# C.net
KiCad netlist of a schematic drawn in EasyEDA Pro
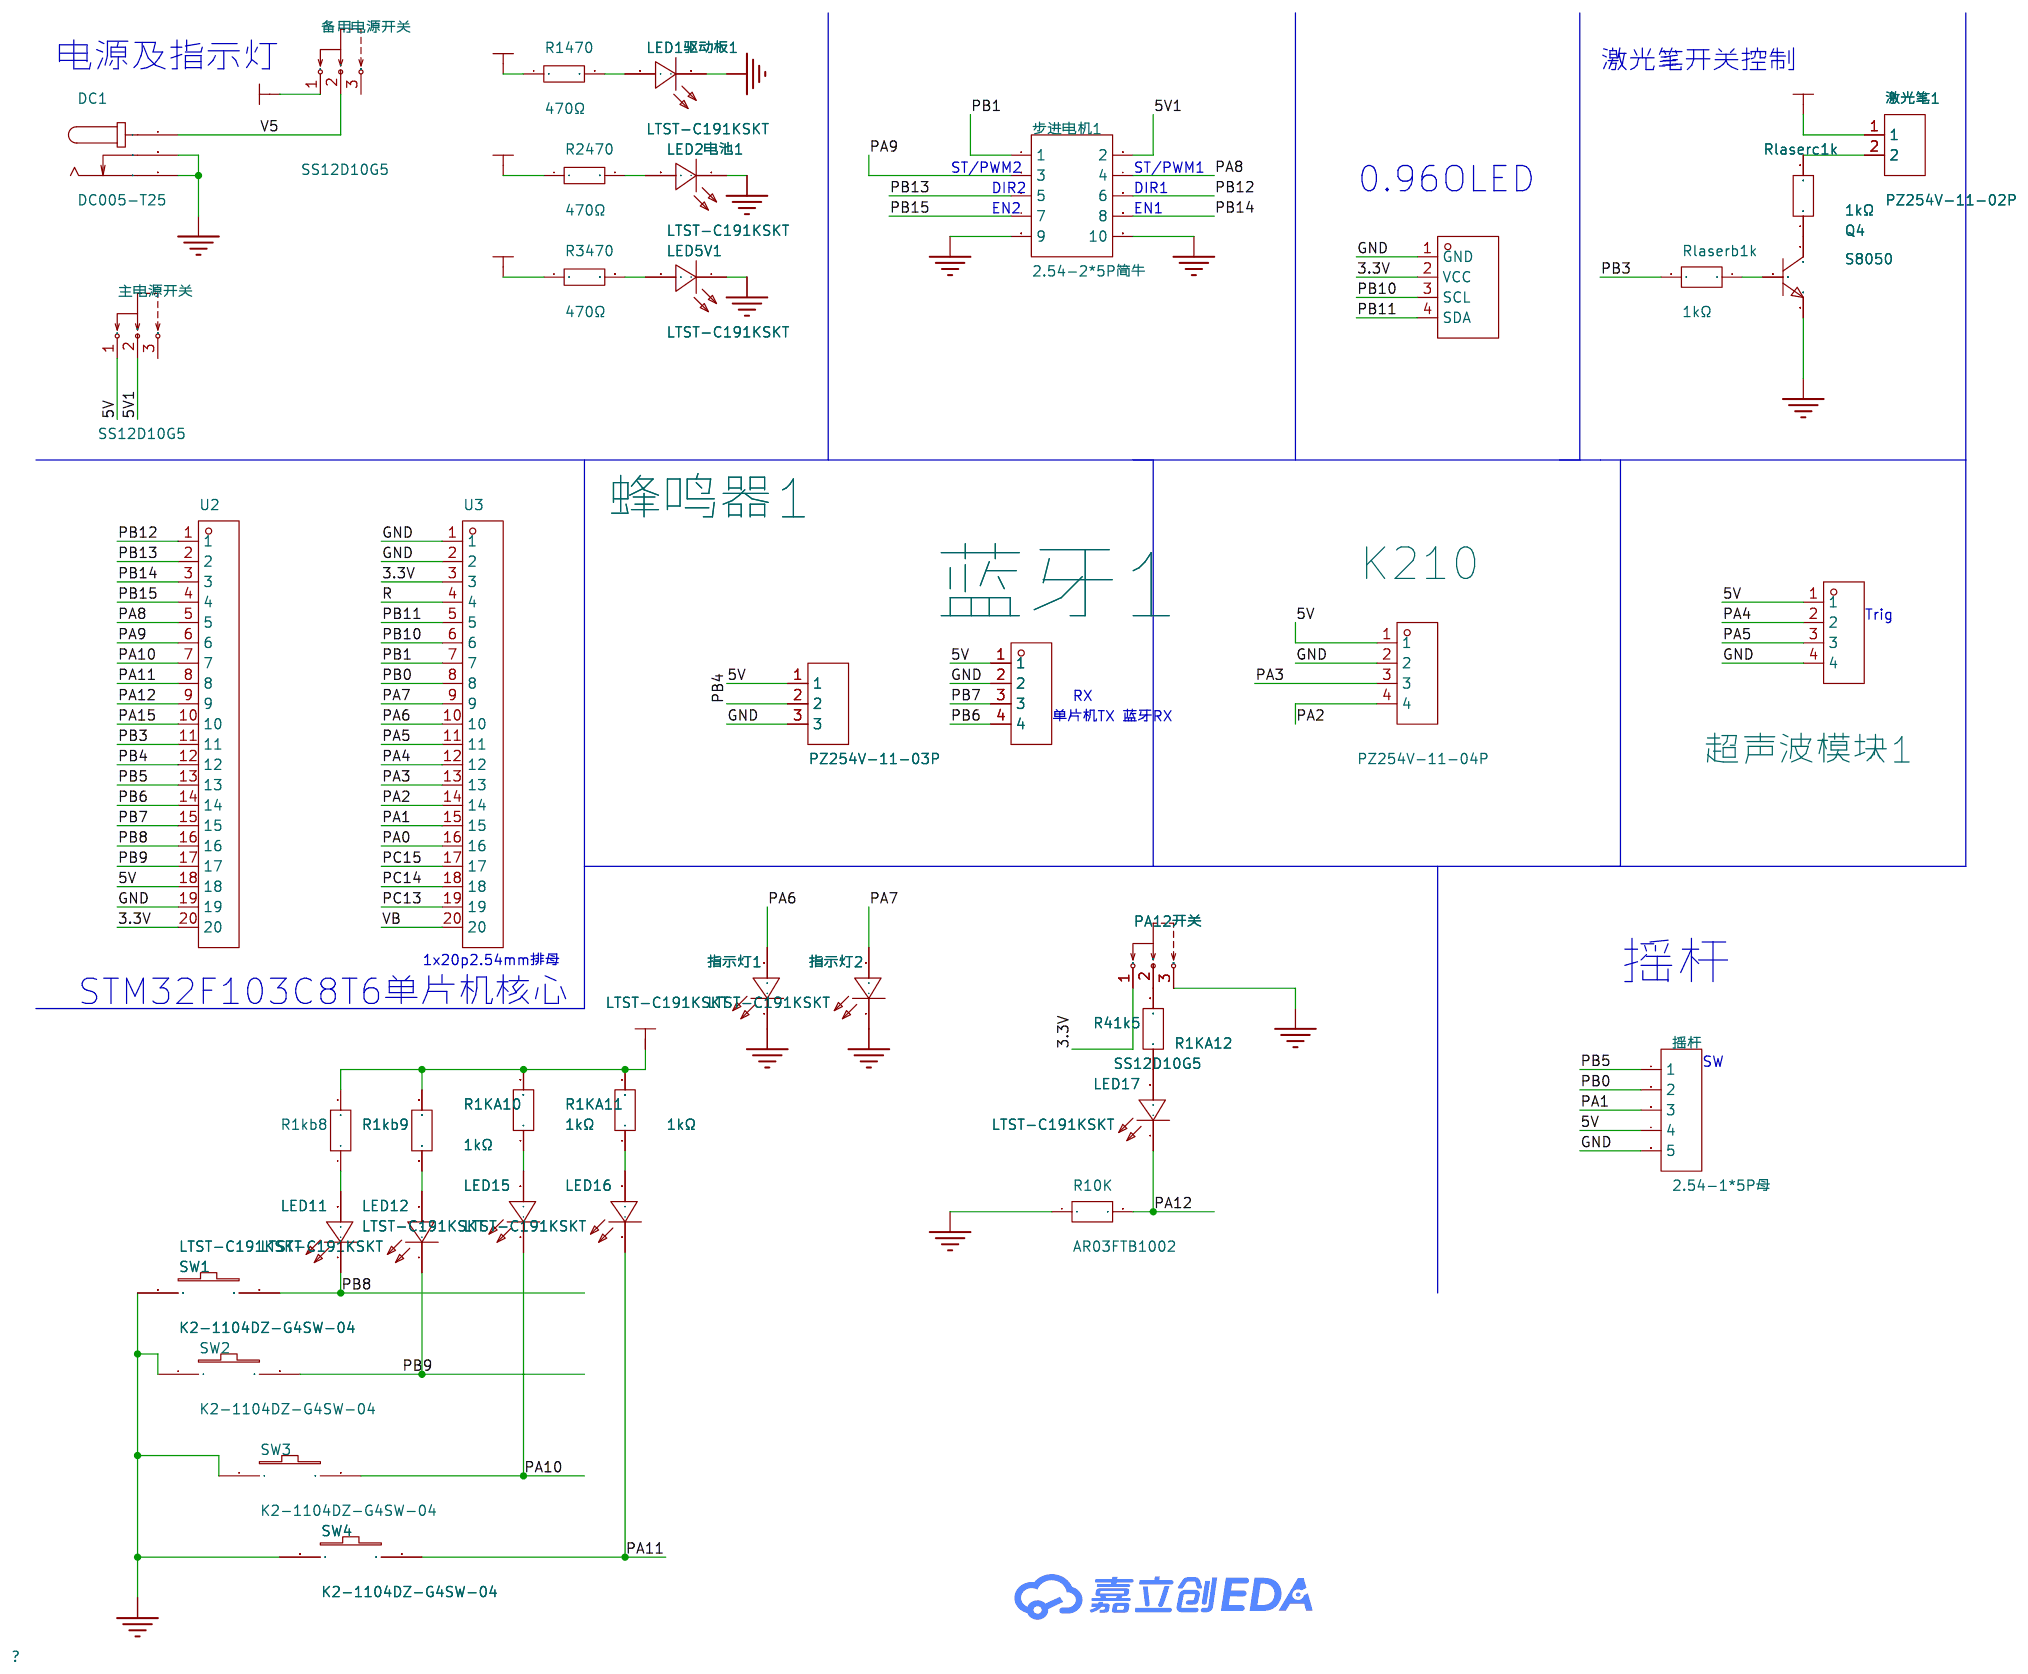
[diagram p0: schematic sheet]

(export (version "E")
  (design (tool "Eeschema 10.0.6"))
  (components
    (comp (ref "DC1")
      (value "DC005-T25")
      (footprint "easyedapro:DC-IN-TH_DC-005-20A-1")
      (description "触点内径:2.5mm;触点外径:6.3mm;额定电流:-;额定电压:-;")
      (fields (field (name "Manufacturer") "SOFNG(硕方)"))
      (libsource (lib "easyedapro") (part "DC005-2.5MM"))
    )
    (comp (ref "K210")
      (value "PZ254V-11-04P")
      (footprint "easyedapro:HDR-TH_4P-P2.54-V-M")
      (fields (field (name "Manufacturer") "XFCN(兴飞)"))
      (libsource (lib "easyedapro") (part "PZ254V-11-04P_C2691448"))
    )
    (comp (ref "LED1驱动板1")
      (value "LTST-C191KSKT")
      (footprint "easyedapro:LED0603-RD-YELLOW")
      (fields (field (name "Manufacturer") "LITEON(光宝)"))
      (libsource (lib "easyedapro") (part "LTST-C191KSKT"))
    )
    (comp (ref "LED2电池1")
      (value "LTST-C191KSKT")
      (footprint "easyedapro:LED0603-RD-YELLOW")
      (fields (field (name "Manufacturer") "LITEON(光宝)"))
      (libsource (lib "easyedapro") (part "LTST-C191KSKT"))
    )
    (comp (ref "LED5V1")
      (value "LTST-C191KSKT")
      (footprint "easyedapro:LED0603-RD-YELLOW")
      (fields (field (name "Manufacturer") "LITEON(光宝)"))
      (libsource (lib "easyedapro") (part "LTST-C191KSKT"))
    )
    (comp (ref "LED11")
      (value "LTST-C191KSKT")
      (footprint "easyedapro:LED0603-RD-YELLOW")
      (fields (field (name "Manufacturer") "LITEON(光宝)"))
      (libsource (lib "easyedapro") (part "LTST-C191KSKT"))
    )
    (comp (ref "LED12")
      (value "LTST-C191KSKT")
      (footprint "easyedapro:LED0603-RD-YELLOW")
      (fields (field (name "Manufacturer") "LITEON(光宝)"))
      (libsource (lib "easyedapro") (part "LTST-C191KSKT"))
    )
    (comp (ref "LED15")
      (value "LTST-C191KSKT")
      (footprint "easyedapro:LED0603-RD-YELLOW")
      (fields (field (name "Manufacturer") "LITEON(光宝)"))
      (libsource (lib "easyedapro") (part "LTST-C191KSKT"))
    )
    (comp (ref "LED16")
      (value "LTST-C191KSKT")
      (footprint "easyedapro:LED0603-RD-YELLOW")
      (fields (field (name "Manufacturer") "LITEON(光宝)"))
      (libsource (lib "easyedapro") (part "LTST-C191KSKT"))
    )
    (comp (ref "LED17")
      (value "LTST-C191KSKT")
      (footprint "easyedapro:LED0603-RD-YELLOW")
      (fields (field (name "Manufacturer") "LITEON(光宝)"))
      (libsource (lib "easyedapro") (part "LTST-C191KSKT"))
    )
    (comp (ref "OLED1")
      (value "HS96L03W2C03")
      (footprint "easyedapro:OLED-TH_L27.8-W27.2-P2.54_C9900033791")
      (description "主控芯片:SSD1315;接口类型:I2C;尺寸(inch):0.96;像素分辨率:128x64;")
      (fields (field (name "Manufacturer") "HS(汉昇)"))
      (libsource (lib "easyedapro") (part "HS96L03W2C03"))
    )
    (comp (ref "PA12开关")
      (value "SS12D10G5")
      (footprint "easyedapro:SW-TH_SHOU-HAN_SS12D10G4")
      (description "电路结构:单刀双掷;安装方式:直插;额定电流(DC):2A;额定电压(DC):125V;机械寿命:3千次;")
      (fields (field (name "Manufacturer") "SHOU HAN(首韩)"))
      (libsource (lib "easyedapro") (part "SS12D10G5"))
    )
    (comp (ref "Q4")
      (value "S8050")
      (footprint "easyedapro:SOT-23-3_L2.9-W1.6-P1.90-LS2.8-BR")
      (description "晶体管类型:NPN;集电极电流(Ic):500mA;集射极击穿电压(Vceo):25V;功率(Pd):300mW;")
      (fields (field (name "Manufacturer") "Hottech(合科泰)"))
      (libsource (lib "easyedapro") (part "S8050_C181158"))
    )
    (comp (ref "R1KA10")
      (value "1kΩ")
      (footprint "easyedapro:R0603")
      (description "电阻类型:厚膜电阻;阻值:1kΩ;精度:±1%;功率:100mW;最大工作电压:75V;")
      (fields (field (name "Manufacturer Part") "FCR0603F1K") (field (name "Manufacturer") "VO(翔胜)"))
      (libsource (lib "easyedapro") (part "FCR0603F1K"))
    )
    (comp (ref "R1KA11")
      (value "1kΩ")
      (footprint "easyedapro:R0603")
      (description "电阻类型:厚膜电阻;阻值:1kΩ;精度:±1%;功率:100mW;最大工作电压:75V;")
      (fields (field (name "Manufacturer Part") "FCR0603F1K") (field (name "Manufacturer") "VO(翔胜)"))
      (libsource (lib "easyedapro") (part "FCR0603F1K"))
    )
    (comp (ref "R1kb8")
      (value "1kΩ")
      (footprint "easyedapro:R0603")
      (description "电阻类型:厚膜电阻;阻值:1kΩ;精度:±1%;功率:100mW;最大工作电压:75V;")
      (fields (field (name "Manufacturer Part") "FCR0603F1K") (field (name "Manufacturer") "VO(翔胜)"))
      (libsource (lib "easyedapro") (part "FCR0603F1K"))
    )
    (comp (ref "R1kb9")
      (value "1kΩ")
      (footprint "easyedapro:R0603")
      (description "电阻类型:厚膜电阻;阻值:1kΩ;精度:±1%;功率:100mW;最大工作电压:75V;")
      (fields (field (name "Manufacturer Part") "FCR0603F1K") (field (name "Manufacturer") "VO(翔胜)"))
      (libsource (lib "easyedapro") (part "FCR0603F1K"))
    )
    (comp (ref "R10K")
      (value "AR03FTB1002")
      (footprint "easyedapro:R0603")
      (fields (field (name "Manufacturer") "Viking(光颉)"))
      (libsource (lib "easyedapro") (part "AR03FTB1002"))
    )
    (comp (ref "R41k5")
      (value "1kΩ")
      (footprint "easyedapro:R0603")
      (description "电阻类型:厚膜电阻;阻值:1kΩ;精度:±1%;功率:100mW;最大工作电压:75V;")
      (fields (field (name "Manufacturer Part") "FCR0603F1K") (field (name "Manufacturer") "VO(翔胜)"))
      (libsource (lib "easyedapro") (part "FCR0603F1K"))
    )
    (comp (ref "R1470")
      (value "470Ω")
      (footprint "easyedapro:R0603")
      (description "电阻类型:厚膜电阻;阻值:470Ω;精度:±1%;功率:100mW;最大工作电压:75V;温度系数:±100ppm/°C;")
      (fields
        (field (name "Manufacturer Part") "0603WAF4700T5E")
        (field (name "Manufacturer") "UNI-ROYAL(厚声)")
      )
      (libsource (lib "easyedapro") (part "0603WAF4700T5E"))
    )
    (comp (ref "R2470")
      (value "470Ω")
      (footprint "easyedapro:R0603")
      (description "电阻类型:厚膜电阻;阻值:470Ω;精度:±1%;功率:100mW;最大工作电压:75V;温度系数:±100ppm/°C;")
      (fields
        (field (name "Manufacturer Part") "0603WAF4700T5E")
        (field (name "Manufacturer") "UNI-ROYAL(厚声)")
      )
      (libsource (lib "easyedapro") (part "0603WAF4700T5E"))
    )
    (comp (ref "R3470")
      (value "470Ω")
      (footprint "easyedapro:R0603")
      (description "电阻类型:厚膜电阻;阻值:470Ω;精度:±1%;功率:100mW;最大工作电压:75V;温度系数:±100ppm/°C;")
      (fields
        (field (name "Manufacturer Part") "0603WAF4700T5E")
        (field (name "Manufacturer") "UNI-ROYAL(厚声)")
      )
      (libsource (lib "easyedapro") (part "0603WAF4700T5E"))
    )
    (comp (ref "Rlaserb1k")
      (value "1kΩ")
      (footprint "easyedapro:R0603")
      (description "电阻类型:厚膜电阻;阻值:1kΩ;精度:±1%;功率:100mW;最大工作电压:75V;")
      (fields (field (name "Manufacturer Part") "FCR0603F1K") (field (name "Manufacturer") "VO(翔胜)"))
      (libsource (lib "easyedapro") (part "FCR0603F1K"))
    )
    (comp (ref "Rlaserc1k")
      (value "1kΩ")
      (footprint "easyedapro:R0603")
      (description "电阻类型:厚膜电阻;阻值:1kΩ;精度:±1%;功率:100mW;最大工作电压:75V;")
      (fields (field (name "Manufacturer Part") "FCR0603F1K") (field (name "Manufacturer") "VO(翔胜)"))
      (libsource (lib "easyedapro") (part "FCR0603F1K"))
    )
    (comp (ref "SW1")
      (value "K2-1104DZ-G4SW-04")
      (footprint "easyedapro:KEY-TH_2P-L6.0-W6.0-P5.00")
      (description "作用力:250gf;安装方式:直插;开关长度:6mm;开关宽度:6mm;开关高度:7mm;触点电流:50mA;额定电压(DC):12V;绝缘电阻:100MΩ;机械寿命:10万次;")
      (fields (field (name "Manufacturer") "韩国韩荣"))
      (libsource (lib "easyedapro") (part "K2-1104DZ-G4SW-04"))
    )
    (comp (ref "SW2")
      (value "K2-1104DZ-G4SW-04")
      (footprint "easyedapro:KEY-TH_2P-L6.0-W6.0-P5.00")
      (description "作用力:250gf;安装方式:直插;开关长度:6mm;开关宽度:6mm;开关高度:7mm;触点电流:50mA;额定电压(DC):12V;绝缘电阻:100MΩ;机械寿命:10万次;")
      (fields (field (name "Manufacturer") "韩国韩荣"))
      (libsource (lib "easyedapro") (part "K2-1104DZ-G4SW-04"))
    )
    (comp (ref "SW3")
      (value "K2-1104DZ-G4SW-04")
      (footprint "easyedapro:KEY-TH_2P-L6.0-W6.0-P5.00")
      (description "作用力:250gf;安装方式:直插;开关长度:6mm;开关宽度:6mm;开关高度:7mm;触点电流:50mA;额定电压(DC):12V;绝缘电阻:100MΩ;机械寿命:10万次;")
      (fields (field (name "Manufacturer") "韩国韩荣"))
      (libsource (lib "easyedapro") (part "K2-1104DZ-G4SW-04"))
    )
    (comp (ref "SW4")
      (value "K2-1104DZ-G4SW-04")
      (footprint "easyedapro:KEY-TH_2P-L6.0-W6.0-P5.00")
      (description "作用力:250gf;安装方式:直插;开关长度:6mm;开关宽度:6mm;开关高度:7mm;触点电流:50mA;额定电压(DC):12V;绝缘电阻:100MΩ;机械寿命:10万次;")
      (fields (field (name "Manufacturer") "韩国韩荣"))
      (libsource (lib "easyedapro") (part "K2-1104DZ-G4SW-04"))
    )
    (comp (ref "U2")
      (value "KH-2FH-1X20P-H4.3")
      (footprint "easyedapro:HDR-TH_20P-P2.00-V-F-A")
      (fields (field (name "Manufacturer") "kinghelm(金航标)"))
      (libsource (lib "easyedapro") (part "KH-2FH-1X20P-H4.3"))
    )
    (comp (ref "U3")
      (value "KH-2FH-1X20P-H4.3")
      (footprint "easyedapro:HDR-TH_20P-P2.00-V-F-A")
      (fields (field (name "Manufacturer") "kinghelm(金航标)"))
      (libsource (lib "easyedapro") (part "KH-2FH-1X20P-H4.3"))
    )
    (comp (ref "主电源开关")
      (value "SS12D10G5")
      (footprint "easyedapro:SW-TH_SHOU-HAN_SS12D10G4")
      (description "电路结构:单刀双掷;安装方式:直插;额定电流(DC):2A;额定电压(DC):125V;机械寿命:3千次;")
      (fields (field (name "Manufacturer") "SHOU HAN(首韩)"))
      (libsource (lib "easyedapro") (part "SS12D10G5"))
    )
    (comp (ref "备用电源开关")
      (value "SS12D10G5")
      (footprint "easyedapro:SW-TH_SHOU-HAN_SS12D10G4")
      (description "电路结构:单刀双掷;安装方式:直插;额定电流(DC):2A;额定电压(DC):125V;机械寿命:3千次;")
      (fields (field (name "Manufacturer") "SHOU HAN(首韩)"))
      (libsource (lib "easyedapro") (part "SS12D10G5"))
    )
    (comp (ref "指示灯1")
      (value "LTST-C191KSKT")
      (footprint "easyedapro:LED0603-RD-YELLOW")
      (fields (field (name "Manufacturer") "LITEON(光宝)"))
      (libsource (lib "easyedapro") (part "LTST-C191KSKT"))
    )
    (comp (ref "指示灯2")
      (value "LTST-C191KSKT")
      (footprint "easyedapro:LED0603-RD-YELLOW")
      (fields (field (name "Manufacturer") "LITEON(光宝)"))
      (libsource (lib "easyedapro") (part "LTST-C191KSKT"))
    )
    (comp (ref "摇杆")
      (value "2.54-1*5P母")
      (footprint "easyedapro:HDR-TH_5P-P2.54-V-F")
      (description "插孔结构:1x5P;间距:2.54mm;行距:-;安装类型:直插;排数:单排;总孔位数:5P;塑高:-;触头材质:-;触头镀层:-;")
      (fields (field (name "Manufacturer") "BOOMELE(博穆精密)"))
      (libsource (lib "easyedapro") (part "Header-Female-2.54_1x5"))
    )
    (comp (ref "步进电机1")
      (value "2.54-2*5P简牛")
      (footprint "easyedapro:IDC-TH_10P-P2.54_C5665")
      (description "连接器类型:简牛座;间距:2.54mm;结构:2x5P;封装形式:直插;行距:2.54mm;排数:2;每排PIN数:5;触头材质:-;触头镀层:-;")
      (fields (field (name "Manufacturer") "BOOMELE(博穆精密)"))
      (libsource (lib "easyedapro") (part "HDR-IDC-2.54-2X5P"))
    )
    (comp (ref "激光笔1")
      (value "PZ254V-11-02P")
      (footprint "easyedapro:HDR-TH_2P-P2.54-V-M")
      (fields (field (name "Manufacturer") "XFCN(兴飞)"))
      (libsource (lib "easyedapro") (part "PZ254V-11-02P"))
    )
    (comp (ref "蓝牙1")
      (value "2.54-1*4P母")
      (footprint "easyedapro:HDR-TH_4P-P2.54-V-F")
      (fields (field (name "Manufacturer") "BOOMELE(博穆精密)"))
      (libsource (lib "easyedapro") (part "2.54-1*4P母"))
    )
    (comp (ref "蜂鸣器1")
      (value "PZ254V-11-03P")
      (footprint "easyedapro:HDR-TH_3P-P2.54-V-M")
      (fields (field (name "Manufacturer") "XFCN(兴飞)"))
      (libsource (lib "easyedapro") (part "PZ254V-11-03P_C2937625"))
    )
    (comp (ref "超声波模块1")
      (value "KH-2.54FH-1X4P-H8.5")
      (footprint "easyedapro:HDR-TH_4P-P2.54-V-F")
      (fields (field (name "Manufacturer") "kinghelm(金航标)"))
      (libsource (lib "easyedapro") (part "KH-2.54FH-1X4P-H8.5"))
    )
  )
  (nets
    (net (code "1") (name "/PA0") (class "Default")
      (node (ref "U3") (pin "16") (pinfunction "16_16") (pintype "unspecified"))
    )
    (net (code "2") (name "/PA1") (class "Default")
      (node (ref "U3") (pin "15") (pinfunction "15_15") (pintype "unspecified"))
      (node (ref "摇杆") (pin "3") (pinfunction "3_3") (pintype "input"))
    )
    (net (code "3") (name "/PA2") (class "Default")
      (node (ref "K210") (pin "4") (pinfunction "4_4") (pintype "unspecified"))
      (node (ref "U3") (pin "14") (pinfunction "14_14") (pintype "unspecified"))
    )
    (net (code "4") (name "/PA3") (class "Default")
      (node (ref "K210") (pin "3") (pinfunction "3_3") (pintype "unspecified"))
      (node (ref "U3") (pin "13") (pinfunction "13_13") (pintype "unspecified"))
    )
    (net (code "5") (name "/PA4") (class "Default")
      (node (ref "U3") (pin "12") (pinfunction "12_12") (pintype "unspecified"))
      (node (ref "超声波模块1") (pin "2") (pinfunction "2_2") (pintype "unspecified"))
    )
    (net (code "6") (name "/PA5") (class "Default")
      (node (ref "U3") (pin "11") (pinfunction "11_11") (pintype "unspecified"))
      (node (ref "超声波模块1") (pin "3") (pinfunction "3_3") (pintype "unspecified"))
    )
    (net (code "7") (name "/PA6") (class "Default")
      (node (ref "U3") (pin "10") (pinfunction "10_10") (pintype "unspecified"))
      (node (ref "指示灯1") (pin "2") (pinfunction "+_2") (pintype "unspecified"))
    )
    (net (code "8") (name "/PA7") (class "Default")
      (node (ref "U3") (pin "9") (pinfunction "9_9") (pintype "unspecified"))
      (node (ref "指示灯2") (pin "2") (pinfunction "+_2") (pintype "unspecified"))
    )
    (net (code "9") (name "/PA8") (class "Default")
      (node (ref "U2") (pin "5") (pinfunction "5_5") (pintype "unspecified"))
      (node (ref "步进电机1") (pin "4") (pinfunction "4_4") (pintype "unspecified"))
    )
    (net (code "10") (name "/PA9") (class "Default")
      (node (ref "U2") (pin "6") (pinfunction "6_6") (pintype "unspecified"))
      (node (ref "步进电机1") (pin "3") (pinfunction "3_3") (pintype "unspecified"))
    )
    (net (code "11") (name "/PA10") (class "Default")
      (node (ref "LED15") (pin "1") (pinfunction "-_1") (pintype "unspecified"))
      (node (ref "SW3") (pin "2") (pinfunction "2_2") (pintype "input"))
      (node (ref "U2") (pin "7") (pinfunction "7_7") (pintype "unspecified"))
    )
    (net (code "12") (name "/PA11") (class "Default")
      (node (ref "LED16") (pin "1") (pinfunction "-_1") (pintype "unspecified"))
      (node (ref "SW4") (pin "2") (pinfunction "2_2") (pintype "input"))
      (node (ref "U2") (pin "8") (pinfunction "8_8") (pintype "unspecified"))
    )
    (net (code "13") (name "/PA12") (class "Default")
      (node (ref "LED17") (pin "1") (pinfunction "-_1") (pintype "unspecified"))
      (node (ref "R10K") (pin "2") (pinfunction "2_2") (pintype "unspecified"))
      (node (ref "U2") (pin "9") (pinfunction "9_9") (pintype "unspecified"))
    )
    (net (code "14") (name "/PA15") (class "Default")
      (node (ref "U2") (pin "10") (pinfunction "10_10") (pintype "unspecified"))
    )
    (net (code "15") (name "/PB0") (class "Default")
      (node (ref "U3") (pin "8") (pinfunction "8_8") (pintype "unspecified"))
      (node (ref "摇杆") (pin "2") (pinfunction "2_2") (pintype "input"))
    )
    (net (code "16") (name "/PB1") (class "Default")
      (node (ref "U3") (pin "7") (pinfunction "7_7") (pintype "unspecified"))
      (node (ref "步进电机1") (pin "1") (pinfunction "1_1") (pintype "unspecified"))
    )
    (net (code "17") (name "/PB3") (class "Default")
      (node (ref "Rlaserb1k") (pin "2") (pinfunction "2_2") (pintype "unspecified"))
      (node (ref "U2") (pin "11") (pinfunction "11_11") (pintype "unspecified"))
    )
    (net (code "18") (name "/PB4") (class "Default")
      (node (ref "U2") (pin "12") (pinfunction "12_12") (pintype "unspecified"))
      (node (ref "蜂鸣器1") (pin "2") (pinfunction "2_2") (pintype "unspecified"))
    )
    (net (code "19") (name "/PB5") (class "Default")
      (node (ref "U2") (pin "13") (pinfunction "13_13") (pintype "unspecified"))
      (node (ref "摇杆") (pin "1") (pinfunction "1_1") (pintype "input"))
    )
    (net (code "20") (name "/PB6") (class "Default")
      (node (ref "U2") (pin "14") (pinfunction "14_14") (pintype "unspecified"))
      (node (ref "蓝牙1") (pin "4") (pinfunction "4_4") (pintype "unspecified"))
    )
    (net (code "21") (name "/PB7") (class "Default")
      (node (ref "U2") (pin "15") (pinfunction "15_15") (pintype "unspecified"))
      (node (ref "蓝牙1") (pin "3") (pinfunction "3_3") (pintype "unspecified"))
    )
    (net (code "22") (name "/PB8") (class "Default")
      (node (ref "LED11") (pin "1") (pinfunction "-_1") (pintype "unspecified"))
      (node (ref "SW1") (pin "2") (pinfunction "2_2") (pintype "input"))
      (node (ref "U2") (pin "16") (pinfunction "16_16") (pintype "unspecified"))
    )
    (net (code "23") (name "/PB9") (class "Default")
      (node (ref "LED12") (pin "1") (pinfunction "-_1") (pintype "unspecified"))
      (node (ref "SW2") (pin "2") (pinfunction "2_2") (pintype "input"))
      (node (ref "U2") (pin "17") (pinfunction "17_17") (pintype "unspecified"))
    )
    (net (code "24") (name "/PB10") (class "Default")
      (node (ref "OLED1") (pin "3") (pinfunction "SCL_3") (pintype "unspecified"))
      (node (ref "U3") (pin "6") (pinfunction "6_6") (pintype "unspecified"))
    )
    (net (code "25") (name "/PB11") (class "Default")
      (node (ref "OLED1") (pin "4") (pinfunction "SDA_4") (pintype "unspecified"))
      (node (ref "U3") (pin "5") (pinfunction "5_5") (pintype "unspecified"))
    )
    (net (code "26") (name "/PB12") (class "Default")
      (node (ref "U2") (pin "1") (pinfunction "1_1") (pintype "unspecified"))
      (node (ref "步进电机1") (pin "6") (pinfunction "6_6") (pintype "unspecified"))
    )
    (net (code "27") (name "/PB13") (class "Default")
      (node (ref "U2") (pin "2") (pinfunction "2_2") (pintype "unspecified"))
      (node (ref "步进电机1") (pin "5") (pinfunction "5_5") (pintype "unspecified"))
    )
    (net (code "28") (name "/PB14") (class "Default")
      (node (ref "U2") (pin "3") (pinfunction "3_3") (pintype "unspecified"))
      (node (ref "步进电机1") (pin "8") (pinfunction "8_8") (pintype "unspecified"))
    )
    (net (code "29") (name "/PB15") (class "Default")
      (node (ref "U2") (pin "4") (pinfunction "4_4") (pintype "unspecified"))
      (node (ref "步进电机1") (pin "7") (pinfunction "7_7") (pintype "unspecified"))
    )
    (net (code "30") (name "/PC13") (class "Default")
      (node (ref "U3") (pin "19") (pinfunction "19_19") (pintype "unspecified"))
    )
    (net (code "31") (name "/PC14") (class "Default")
      (node (ref "U3") (pin "18") (pinfunction "18_18") (pintype "unspecified"))
    )
    (net (code "32") (name "/PC15") (class "Default")
      (node (ref "U3") (pin "17") (pinfunction "17_17") (pintype "unspecified"))
    )
    (net (code "33") (name "/R") (class "Default")
      (node (ref "U3") (pin "4") (pinfunction "4_4") (pintype "unspecified"))
    )
    (net (code "34") (name "/VB") (class "Default")
      (node (ref "U3") (pin "20") (pinfunction "20_20") (pintype "unspecified"))
    )
    (net (code "35") (name "3.3V") (class "Default")
      (node (ref "OLED1") (pin "2") (pinfunction "VCC_2") (pintype "unspecified"))
      (node (ref "PA12开关") (pin "1") (pinfunction "1_1") (pintype "unspecified"))
      (node (ref "R1KA10") (pin "2") (pinfunction "2_2") (pintype "unspecified"))
      (node (ref "R1KA11") (pin "2") (pinfunction "2_2") (pintype "unspecified"))
      (node (ref "R1kb8") (pin "2") (pinfunction "2_2") (pintype "unspecified"))
      (node (ref "R1kb9") (pin "2") (pinfunction "2_2") (pintype "unspecified"))
      (node (ref "U2") (pin "20") (pinfunction "20_20") (pintype "unspecified"))
      (node (ref "U3") (pin "3") (pinfunction "3_3") (pintype "unspecified"))
    )
    (net (code "36") (name "5V") (class "Default")
      (node (ref "K210") (pin "1") (pinfunction "1_1") (pintype "unspecified"))
      (node (ref "R3470") (pin "1") (pinfunction "1_1") (pintype "input"))
      (node (ref "U2") (pin "18") (pinfunction "18_18") (pintype "unspecified"))
      (node (ref "主电源开关") (pin "1") (pinfunction "1_1") (pintype "unspecified"))
      (node (ref "备用电源开关") (pin "1") (pinfunction "1_1") (pintype "unspecified"))
      (node (ref "摇杆") (pin "4") (pinfunction "4_4") (pintype "input"))
      (node (ref "激光笔1") (pin "1") (pinfunction "1_1") (pintype "unspecified"))
      (node (ref "蓝牙1") (pin "1") (pinfunction "1_1") (pintype "unspecified"))
      (node (ref "蜂鸣器1") (pin "1") (pinfunction "1_1") (pintype "unspecified"))
      (node (ref "超声波模块1") (pin "1") (pinfunction "1_1") (pintype "unspecified"))
    )
    (net (code "37") (name "5V1") (class "Default")
      (node (ref "R1470") (pin "1") (pinfunction "1_1") (pintype "input"))
      (node (ref "主电源开关") (pin "2") (pinfunction "2_2") (pintype "unspecified"))
      (node (ref "步进电机1") (pin "2") (pinfunction "2_2") (pintype "unspecified"))
    )
    (net (code "38") (name "GND") (class "Default")
      (node (ref "DC1") (pin "2") (pinfunction "2_2") (pintype "unspecified"))
      (node (ref "DC1") (pin "3") (pinfunction "3_3") (pintype "unspecified"))
      (node (ref "K210") (pin "2") (pinfunction "2_2") (pintype "unspecified"))
      (node (ref "LED1驱动板1") (pin "1") (pinfunction "-_1") (pintype "unspecified"))
      (node (ref "LED2电池1") (pin "1") (pinfunction "-_1") (pintype "unspecified"))
      (node (ref "LED5V1") (pin "1") (pinfunction "-_1") (pintype "unspecified"))
      (node (ref "OLED1") (pin "1") (pinfunction "GND_1") (pintype "unspecified"))
      (node (ref "PA12开关") (pin "3") (pinfunction "3_3") (pintype "unspecified"))
      (node (ref "Q4") (pin "2") (pinfunction "2_2") (pintype "input"))
      (node (ref "R10K") (pin "1") (pinfunction "1_1") (pintype "unspecified"))
      (node (ref "SW1") (pin "1") (pinfunction "1_1") (pintype "input"))
      (node (ref "SW2") (pin "1") (pinfunction "1_1") (pintype "input"))
      (node (ref "SW3") (pin "1") (pinfunction "1_1") (pintype "input"))
      (node (ref "SW4") (pin "1") (pinfunction "1_1") (pintype "input"))
      (node (ref "U2") (pin "19") (pinfunction "19_19") (pintype "unspecified"))
      (node (ref "U3") (pin "1") (pinfunction "1_1") (pintype "unspecified"))
      (node (ref "U3") (pin "2") (pinfunction "2_2") (pintype "unspecified"))
      (node (ref "指示灯1") (pin "1") (pinfunction "-_1") (pintype "unspecified"))
      (node (ref "指示灯2") (pin "1") (pinfunction "-_1") (pintype "unspecified"))
      (node (ref "摇杆") (pin "5") (pinfunction "5_5") (pintype "input"))
      (node (ref "步进电机1") (pin "10") (pinfunction "10_10") (pintype "unspecified"))
      (node (ref "步进电机1") (pin "9") (pinfunction "9_9") (pintype "unspecified"))
      (node (ref "蓝牙1") (pin "2") (pinfunction "2_2") (pintype "unspecified"))
      (node (ref "蜂鸣器1") (pin "3") (pinfunction "3_3") (pintype "unspecified"))
      (node (ref "超声波模块1") (pin "4") (pinfunction "4_4") (pintype "unspecified"))
    )
    (net (code "39") (name "Net-(LED1驱动板1-+)") (class "Default")
      (node (ref "LED1驱动板1") (pin "2") (pinfunction "+_2") (pintype "unspecified"))
      (node (ref "R1470") (pin "2") (pinfunction "2_2") (pintype "input"))
    )
    (net (code "40") (name "Net-(LED2电池1-+)") (class "Default")
      (node (ref "LED2电池1") (pin "2") (pinfunction "+_2") (pintype "unspecified"))
      (node (ref "R2470") (pin "2") (pinfunction "2_2") (pintype "input"))
    )
    (net (code "41") (name "Net-(LED5V1-+)") (class "Default")
      (node (ref "LED5V1") (pin "2") (pinfunction "+_2") (pintype "unspecified"))
      (node (ref "R3470") (pin "2") (pinfunction "2_2") (pintype "input"))
    )
    (net (code "42") (name "Net-(LED11-+)") (class "Default")
      (node (ref "LED11") (pin "2") (pinfunction "+_2") (pintype "unspecified"))
      (node (ref "R1kb8") (pin "1") (pinfunction "1_1") (pintype "unspecified"))
    )
    (net (code "43") (name "Net-(LED12-+)") (class "Default")
      (node (ref "LED12") (pin "2") (pinfunction "+_2") (pintype "unspecified"))
      (node (ref "R1kb9") (pin "1") (pinfunction "1_1") (pintype "unspecified"))
    )
    (net (code "44") (name "Net-(LED15-+)") (class "Default")
      (node (ref "LED15") (pin "2") (pinfunction "+_2") (pintype "unspecified"))
      (node (ref "R1KA10") (pin "1") (pinfunction "1_1") (pintype "unspecified"))
    )
    (net (code "45") (name "Net-(LED16-+)") (class "Default")
      (node (ref "LED16") (pin "2") (pinfunction "+_2") (pintype "unspecified"))
      (node (ref "R1KA11") (pin "1") (pinfunction "1_1") (pintype "unspecified"))
    )
    (net (code "46") (name "Net-(LED17-+)") (class "Default")
      (node (ref "LED17") (pin "2") (pinfunction "+_2") (pintype "unspecified"))
      (node (ref "R41k5") (pin "1") (pinfunction "1_1") (pintype "unspecified"))
    )
    (net (code "47") (name "Net-(PA12开关-Pad2)") (class "Default")
      (node (ref "PA12开关") (pin "2") (pinfunction "2_2") (pintype "unspecified"))
      (node (ref "R41k5") (pin "2") (pinfunction "2_2") (pintype "unspecified"))
    )
    (net (code "48") (name "Net-(Q4-Pad1)") (class "Default")
      (node (ref "Q4") (pin "1") (pinfunction "1_1") (pintype "input"))
      (node (ref "Rlaserb1k") (pin "1") (pinfunction "1_1") (pintype "unspecified"))
    )
    (net (code "49") (name "Net-(Q4-Pad3)") (class "Default")
      (node (ref "Q4") (pin "3") (pinfunction "3_3") (pintype "input"))
      (node (ref "Rlaserc1k") (pin "1") (pinfunction "1_1") (pintype "unspecified"))
    )
    (net (code "50") (name "Net-(Rlaserc1k-Pad2)") (class "Default")
      (node (ref "Rlaserc1k") (pin "2") (pinfunction "2_2") (pintype "unspecified"))
      (node (ref "激光笔1") (pin "2") (pinfunction "2_2") (pintype "unspecified"))
    )
    (net (code "51") (name "V5") (class "Default")
      (node (ref "DC1") (pin "1") (pinfunction "1_1") (pintype "unspecified"))
      (node (ref "R2470") (pin "1") (pinfunction "1_1") (pintype "input"))
      (node (ref "备用电源开关") (pin "2") (pinfunction "2_2") (pintype "unspecified"))
    )
    (net (code "52") (name "unconnected-(主电源开关-Pad3)") (class "Default")
      (node (ref "主电源开关") (pin "3") (pinfunction "3_3") (pintype "unspecified"))
    )
    (net (code "53") (name "unconnected-(备用电源开关-Pad3)") (class "Default")
      (node (ref "备用电源开关") (pin "3") (pinfunction "3_3") (pintype "unspecified"))
    )
  )
)
